# fretscanner2.net
KiCad netlist of a schematic drawn in EAGLE
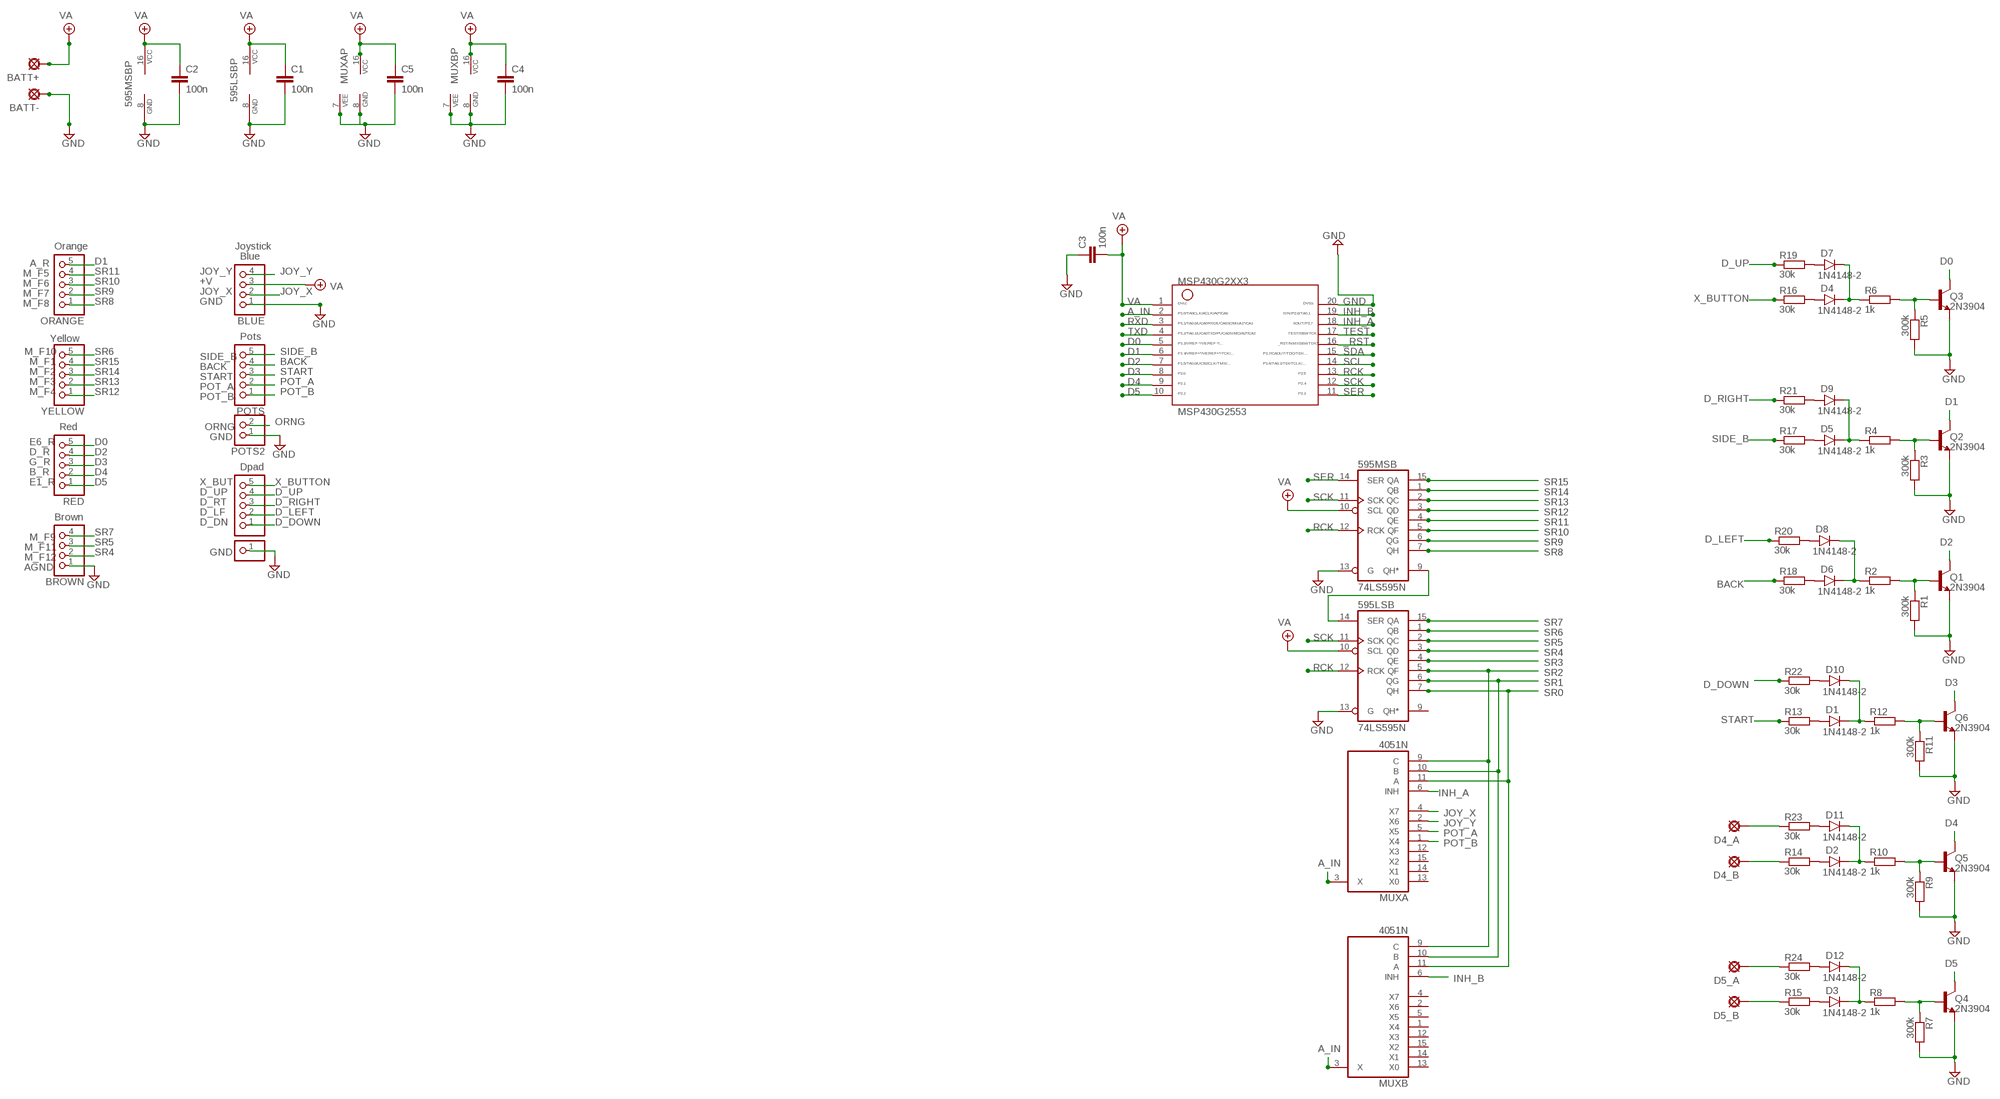
[diagram p0: schematic, sheet 1]

(export (version "E")
  (design (tool "Eeschema 10.0.6"))
  (components
    (comp (ref "595LSB")
      (value "74LS595N")
      (footprint "eagle-import:DIL16")
      (libsource (lib "eagle-import") (part "74595NLS"))
    )
    (comp (ref "595MSB")
      (value "74LS595N")
      (footprint "eagle-import:DIL16")
      (libsource (lib "eagle-import") (part "74595NLS"))
    )
    (comp (ref "BATT+")
      (value "PADL")
      (footprint "eagle-import:LONG")
      (libsource (lib "eagle-import") (part "PADL"))
    )
    (comp (ref "BATT-")
      (value "PADL")
      (footprint "eagle-import:LONG")
      (libsource (lib "eagle-import") (part "PADL"))
    )
    (comp (ref "BLUE")
      (value "PINHD-1X4")
      (footprint "eagle-import:1X04")
      (libsource (lib "eagle-import") (part "PINHD-1X4"))
    )
    (comp (ref "BROWN")
      (value "PINHD-1X4")
      (footprint "eagle-import:1X04")
      (libsource (lib "eagle-import") (part "PINHD-1X4"))
    )
    (comp (ref "C1")
      (value "100n")
      (footprint "eagle-import:050X030_050_3")
      (libsource (lib "eagle-import") (part "050X030_050"))
    )
    (comp (ref "C2")
      (value "100n")
      (footprint "eagle-import:050X030_050_3")
      (libsource (lib "eagle-import") (part "050X030_050"))
    )
    (comp (ref "C3")
      (value "100n")
      (footprint "eagle-import:050X030_050_3")
      (libsource (lib "eagle-import") (part "050X030_050"))
    )
    (comp (ref "C4")
      (value "100n")
      (footprint "eagle-import:050X030_050_3")
      (libsource (lib "eagle-import") (part "050X030_050"))
    )
    (comp (ref "C5")
      (value "100n")
      (footprint "eagle-import:050X030_050_3")
      (libsource (lib "eagle-import") (part "050X030_050"))
    )
    (comp (ref "D1")
      (value "1N4148-2")
      (footprint "eagle-import:DO35-2")
      (libsource (lib "eagle-import") (part "1N4148-2"))
    )
    (comp (ref "D2")
      (value "1N4148-2")
      (footprint "eagle-import:DO35-2")
      (libsource (lib "eagle-import") (part "1N4148-2"))
    )
    (comp (ref "D3")
      (value "1N4148-2")
      (footprint "eagle-import:DO35-2")
      (libsource (lib "eagle-import") (part "1N4148-2"))
    )
    (comp (ref "D4")
      (value "1N4148-2")
      (footprint "eagle-import:DO35-2")
      (libsource (lib "eagle-import") (part "1N4148-2"))
    )
    (comp (ref "D4_A")
      (value "PAD")
      (footprint "eagle-import:SQUARE")
      (libsource (lib "eagle-import") (part "PAD"))
    )
    (comp (ref "D4_B")
      (value "PAD")
      (footprint "eagle-import:SQUARE")
      (libsource (lib "eagle-import") (part "PAD"))
    )
    (comp (ref "D5")
      (value "1N4148-2")
      (footprint "eagle-import:DO35-2")
      (libsource (lib "eagle-import") (part "1N4148-2"))
    )
    (comp (ref "D5_A")
      (value "PAD")
      (footprint "eagle-import:SQUARE")
      (libsource (lib "eagle-import") (part "PAD"))
    )
    (comp (ref "D5_B")
      (value "PAD")
      (footprint "eagle-import:SQUARE")
      (libsource (lib "eagle-import") (part "PAD"))
    )
    (comp (ref "D6")
      (value "1N4148-2")
      (footprint "eagle-import:DO35-2")
      (libsource (lib "eagle-import") (part "1N4148-2"))
    )
    (comp (ref "D7")
      (value "1N4148-2")
      (footprint "eagle-import:DO35-2")
      (libsource (lib "eagle-import") (part "1N4148-2"))
    )
    (comp (ref "D8")
      (value "1N4148-2")
      (footprint "eagle-import:DO35-2")
      (libsource (lib "eagle-import") (part "1N4148-2"))
    )
    (comp (ref "D9")
      (value "1N4148-2")
      (footprint "eagle-import:DO35-2")
      (libsource (lib "eagle-import") (part "1N4148-2"))
    )
    (comp (ref "D10")
      (value "1N4148-2")
      (footprint "eagle-import:DO35-2")
      (libsource (lib "eagle-import") (part "1N4148-2"))
    )
    (comp (ref "D11")
      (value "1N4148-2")
      (footprint "eagle-import:DO35-2")
      (libsource (lib "eagle-import") (part "1N4148-2"))
    )
    (comp (ref "D12")
      (value "1N4148-2")
      (footprint "eagle-import:DO35-2")
      (libsource (lib "eagle-import") (part "1N4148-2"))
    )
    (comp (ref "DPAD")
      (value "PINHD-1X5")
      (footprint "eagle-import:1X05")
      (libsource (lib "eagle-import") (part "PINHD-1X5"))
    )
    (comp (ref "DPAD2")
      (value "PINHD-1X1")
      (footprint "eagle-import:1X01")
      (libsource (lib "eagle-import") (part "PINHD-1X1"))
    )
    (comp (ref "MSP430G2553")
      (value "G2XX3---N20")
      (footprint "eagle-import:N20")
      (libsource (lib "eagle-import") (part "G2XX3---N20"))
    )
    (comp (ref "MUXA")
      (value "4051N")
      (footprint "eagle-import:DIL16")
      (libsource (lib "eagle-import") (part "4051N"))
    )
    (comp (ref "MUXB")
      (value "4051N")
      (footprint "eagle-import:DIL16")
      (libsource (lib "eagle-import") (part "4051N"))
    )
    (comp (ref "ORANGE")
      (value "PINHD-1X5")
      (footprint "eagle-import:1X05")
      (libsource (lib "eagle-import") (part "PINHD-1X5"))
    )
    (comp (ref "POTS")
      (value "PINHD-1X5")
      (footprint "eagle-import:1X05")
      (libsource (lib "eagle-import") (part "PINHD-1X5"))
    )
    (comp (ref "POTS2")
      (value "PINHD-1X2")
      (footprint "eagle-import:1X02")
      (libsource (lib "eagle-import") (part "PINHD-1X2"))
    )
    (comp (ref "Q1")
      (value "2N3904")
      (footprint "eagle-import:TO92-")
      (libsource (lib "eagle-import") (part "2N3904"))
    )
    (comp (ref "Q2")
      (value "2N3904")
      (footprint "eagle-import:TO92-")
      (libsource (lib "eagle-import") (part "2N3904"))
    )
    (comp (ref "Q3")
      (value "2N3904")
      (footprint "eagle-import:TO92-")
      (libsource (lib "eagle-import") (part "2N3904"))
    )
    (comp (ref "Q4")
      (value "2N3904")
      (footprint "eagle-import:TO92-")
      (libsource (lib "eagle-import") (part "2N3904"))
    )
    (comp (ref "Q5")
      (value "2N3904")
      (footprint "eagle-import:TO92-")
      (libsource (lib "eagle-import") (part "2N3904"))
    )
    (comp (ref "Q6")
      (value "2N3904")
      (footprint "eagle-import:TO92-")
      (libsource (lib "eagle-import") (part "2N3904"))
    )
    (comp (ref "R1")
      (value "300k")
      (footprint "eagle-import:R0207_1V")
      (libsource (lib "eagle-import") (part "6MM-EU1"))
    )
    (comp (ref "R2")
      (value "1k")
      (footprint "eagle-import:R0207_3")
      (libsource (lib "eagle-import") (part "6MM-EU"))
    )
    (comp (ref "R3")
      (value "300k")
      (footprint "eagle-import:R0207_1V")
      (libsource (lib "eagle-import") (part "6MM-EU1"))
    )
    (comp (ref "R4")
      (value "1k")
      (footprint "eagle-import:R0207_3")
      (libsource (lib "eagle-import") (part "6MM-EU"))
    )
    (comp (ref "R5")
      (value "300k")
      (footprint "eagle-import:R0207_1V")
      (libsource (lib "eagle-import") (part "6MM-EU1"))
    )
    (comp (ref "R6")
      (value "1k")
      (footprint "eagle-import:R0207_3")
      (libsource (lib "eagle-import") (part "6MM-EU"))
    )
    (comp (ref "R7")
      (value "300k")
      (footprint "eagle-import:R0207_1V")
      (libsource (lib "eagle-import") (part "6MM-EU1"))
    )
    (comp (ref "R8")
      (value "1k")
      (footprint "eagle-import:R0207_3")
      (libsource (lib "eagle-import") (part "6MM-EU"))
    )
    (comp (ref "R9")
      (value "300k")
      (footprint "eagle-import:R0207_1V")
      (libsource (lib "eagle-import") (part "6MM-EU1"))
    )
    (comp (ref "R10")
      (value "1k")
      (footprint "eagle-import:R0207_3")
      (libsource (lib "eagle-import") (part "6MM-EU"))
    )
    (comp (ref "R11")
      (value "300k")
      (footprint "eagle-import:R0207_1V")
      (libsource (lib "eagle-import") (part "6MM-EU1"))
    )
    (comp (ref "R12")
      (value "1k")
      (footprint "eagle-import:R0207_3")
      (libsource (lib "eagle-import") (part "6MM-EU"))
    )
    (comp (ref "R13")
      (value "30k")
      (footprint "eagle-import:R0207_3")
      (libsource (lib "eagle-import") (part "6MM-EU"))
    )
    (comp (ref "R14")
      (value "30k")
      (footprint "eagle-import:R0207_3")
      (libsource (lib "eagle-import") (part "6MM-EU"))
    )
    (comp (ref "R15")
      (value "30k")
      (footprint "eagle-import:R0207_3")
      (libsource (lib "eagle-import") (part "6MM-EU"))
    )
    (comp (ref "R16")
      (value "30k")
      (footprint "eagle-import:R0207_3")
      (libsource (lib "eagle-import") (part "6MM-EU"))
    )
    (comp (ref "R17")
      (value "30k")
      (footprint "eagle-import:R0207_3")
      (libsource (lib "eagle-import") (part "6MM-EU"))
    )
    (comp (ref "R18")
      (value "30k")
      (footprint "eagle-import:R0207_3")
      (libsource (lib "eagle-import") (part "6MM-EU"))
    )
    (comp (ref "R19")
      (value "30k")
      (footprint "eagle-import:R0207_3")
      (libsource (lib "eagle-import") (part "6MM-EU"))
    )
    (comp (ref "R20")
      (value "30k")
      (footprint "eagle-import:R0207_3")
      (libsource (lib "eagle-import") (part "6MM-EU"))
    )
    (comp (ref "R21")
      (value "30k")
      (footprint "eagle-import:R0207_3")
      (libsource (lib "eagle-import") (part "6MM-EU"))
    )
    (comp (ref "R22")
      (value "30k")
      (footprint "eagle-import:R0207_3")
      (libsource (lib "eagle-import") (part "6MM-EU"))
    )
    (comp (ref "R23")
      (value "30k")
      (footprint "eagle-import:R0207_3")
      (libsource (lib "eagle-import") (part "6MM-EU"))
    )
    (comp (ref "R24")
      (value "30k")
      (footprint "eagle-import:R0207_3")
      (libsource (lib "eagle-import") (part "6MM-EU"))
    )
    (comp (ref "RED")
      (value "PINHD-1X5")
      (footprint "eagle-import:1X05")
      (libsource (lib "eagle-import") (part "PINHD-1X5"))
    )
    (comp (ref "YELLOW")
      (value "PINHD-1X5")
      (footprint "eagle-import:1X05")
      (libsource (lib "eagle-import") (part "PINHD-1X5"))
    )
  )
  (nets
    (net (code "1") (name "/A_IN") (class "Default")
      (node (ref "MSP430G2553") (pin "2") (pinfunction "2_2") (pintype "bidirectional"))
      (node (ref "MUXA") (pin "3") (pinfunction "X_3") (pintype "bidirectional"))
      (node (ref "MUXB") (pin "3") (pinfunction "X_3") (pintype "bidirectional"))
    )
    (net (code "2") (name "/BACK") (class "Default")
      (node (ref "POTS") (pin "4") (pinfunction "4_4") (pintype "passive"))
      (node (ref "R18") (pin "1") (pinfunction "1_1") (pintype "passive"))
    )
    (net (code "3") (name "/D0") (class "Default")
      (node (ref "MSP430G2553") (pin "5") (pinfunction "5_5") (pintype "bidirectional"))
      (node (ref "Q3") (pin "1") (pinfunction "C_1") (pintype "passive"))
      (node (ref "RED") (pin "5") (pinfunction "5_5") (pintype "passive"))
    )
    (net (code "4") (name "/D1") (class "Default")
      (node (ref "MSP430G2553") (pin "6") (pinfunction "6_6") (pintype "bidirectional"))
      (node (ref "ORANGE") (pin "5") (pinfunction "5_5") (pintype "passive"))
      (node (ref "Q2") (pin "1") (pinfunction "C_1") (pintype "passive"))
    )
    (net (code "5") (name "/D2") (class "Default")
      (node (ref "MSP430G2553") (pin "7") (pinfunction "7_7") (pintype "bidirectional"))
      (node (ref "Q1") (pin "1") (pinfunction "C_1") (pintype "passive"))
      (node (ref "RED") (pin "4") (pinfunction "4_4") (pintype "passive"))
    )
    (net (code "6") (name "/D3") (class "Default")
      (node (ref "MSP430G2553") (pin "8") (pinfunction "8_8") (pintype "bidirectional"))
      (node (ref "Q6") (pin "1") (pinfunction "C_1") (pintype "passive"))
      (node (ref "RED") (pin "3") (pinfunction "3_3") (pintype "passive"))
    )
    (net (code "7") (name "/D4") (class "Default")
      (node (ref "MSP430G2553") (pin "9") (pinfunction "9_9") (pintype "bidirectional"))
      (node (ref "Q5") (pin "1") (pinfunction "C_1") (pintype "passive"))
      (node (ref "RED") (pin "2") (pinfunction "2_2") (pintype "passive"))
    )
    (net (code "8") (name "/D5") (class "Default")
      (node (ref "MSP430G2553") (pin "10") (pinfunction "10_10") (pintype "bidirectional"))
      (node (ref "Q4") (pin "1") (pinfunction "C_1") (pintype "passive"))
      (node (ref "RED") (pin "1") (pinfunction "1_1") (pintype "passive"))
    )
    (net (code "9") (name "/D_DOWN") (class "Default")
      (node (ref "DPAD") (pin "1") (pinfunction "1_1") (pintype "passive"))
      (node (ref "R22") (pin "1") (pinfunction "1_1") (pintype "passive"))
    )
    (net (code "10") (name "/D_LEFT") (class "Default")
      (node (ref "DPAD") (pin "2") (pinfunction "2_2") (pintype "passive"))
      (node (ref "R20") (pin "1") (pinfunction "1_1") (pintype "passive"))
    )
    (net (code "11") (name "/D_RIGHT") (class "Default")
      (node (ref "DPAD") (pin "3") (pinfunction "3_3") (pintype "passive"))
      (node (ref "R21") (pin "1") (pinfunction "1_1") (pintype "passive"))
    )
    (net (code "12") (name "/D_UP") (class "Default")
      (node (ref "DPAD") (pin "4") (pinfunction "4_4") (pintype "passive"))
      (node (ref "R19") (pin "1") (pinfunction "1_1") (pintype "passive"))
    )
    (net (code "13") (name "/INH_A") (class "Default")
      (node (ref "MSP430G2553") (pin "18") (pinfunction "18_18") (pintype "bidirectional"))
      (node (ref "MUXA") (pin "6") (pinfunction "INH_6") (pintype "input"))
    )
    (net (code "14") (name "/INH_B") (class "Default")
      (node (ref "MSP430G2553") (pin "19") (pinfunction "19_19") (pintype "bidirectional"))
      (node (ref "MUXB") (pin "6") (pinfunction "INH_6") (pintype "input"))
    )
    (net (code "15") (name "/JOY_X") (class "Default")
      (node (ref "BLUE") (pin "2") (pinfunction "2_2") (pintype "passive"))
      (node (ref "MUXA") (pin "4") (pinfunction "X7_4") (pintype "bidirectional"))
    )
    (net (code "16") (name "/JOY_Y") (class "Default")
      (node (ref "BLUE") (pin "4") (pinfunction "4_4") (pintype "passive"))
      (node (ref "MUXA") (pin "2") (pinfunction "X6_2") (pintype "bidirectional"))
    )
    (net (code "17") (name "/ORNG") (class "Default")
      (node (ref "POTS2") (pin "2") (pinfunction "2_2") (pintype "passive"))
    )
    (net (code "18") (name "/POT_A") (class "Default")
      (node (ref "MUXA") (pin "5") (pinfunction "X5_5") (pintype "bidirectional"))
      (node (ref "POTS") (pin "2") (pinfunction "2_2") (pintype "passive"))
    )
    (net (code "19") (name "/POT_B") (class "Default")
      (node (ref "MUXA") (pin "1") (pinfunction "X4_1") (pintype "bidirectional"))
      (node (ref "POTS") (pin "1") (pinfunction "1_1") (pintype "passive"))
    )
    (net (code "20") (name "/RCK") (class "Default")
      (node (ref "595LSB") (pin "12") (pinfunction "RCK_12") (pintype "input"))
      (node (ref "595MSB") (pin "12") (pinfunction "RCK_12") (pintype "input"))
      (node (ref "MSP430G2553") (pin "13") (pinfunction "13_13") (pintype "bidirectional"))
    )
    (net (code "21") (name "/RXD") (class "Default")
      (node (ref "MSP430G2553") (pin "3") (pinfunction "3_3") (pintype "bidirectional"))
    )
    (net (code "22") (name "/SCK") (class "Default")
      (node (ref "595LSB") (pin "11") (pinfunction "SCK_11") (pintype "input"))
      (node (ref "595MSB") (pin "11") (pinfunction "SCK_11") (pintype "input"))
      (node (ref "MSP430G2553") (pin "12") (pinfunction "12_12") (pintype "bidirectional"))
    )
    (net (code "23") (name "/SCL") (class "Default")
      (node (ref "MSP430G2553") (pin "14") (pinfunction "14_14") (pintype "bidirectional"))
    )
    (net (code "24") (name "/SDA") (class "Default")
      (node (ref "MSP430G2553") (pin "15") (pinfunction "15_15") (pintype "bidirectional"))
    )
    (net (code "25") (name "/SER") (class "Default")
      (node (ref "595MSB") (pin "14") (pinfunction "SER_14") (pintype "input"))
      (node (ref "MSP430G2553") (pin "11") (pinfunction "11_11") (pintype "bidirectional"))
    )
    (net (code "26") (name "/SIDE_B") (class "Default")
      (node (ref "POTS") (pin "5") (pinfunction "5_5") (pintype "passive"))
      (node (ref "R17") (pin "1") (pinfunction "1_1") (pintype "passive"))
    )
    (net (code "27") (name "/SR0") (class "Default")
      (node (ref "595LSB") (pin "7") (pinfunction "QH_7") (pintype "tri_state"))
      (node (ref "MUXA") (pin "11") (pinfunction "A_11") (pintype "input"))
      (node (ref "MUXB") (pin "11") (pinfunction "A_11") (pintype "input"))
    )
    (net (code "28") (name "/SR1") (class "Default")
      (node (ref "595LSB") (pin "6") (pinfunction "QG_6") (pintype "tri_state"))
      (node (ref "MUXA") (pin "10") (pinfunction "B_10") (pintype "input"))
      (node (ref "MUXB") (pin "10") (pinfunction "B_10") (pintype "input"))
    )
    (net (code "29") (name "/SR2") (class "Default")
      (node (ref "595LSB") (pin "5") (pinfunction "QF_5") (pintype "tri_state"))
      (node (ref "MUXA") (pin "9") (pinfunction "C_9") (pintype "input"))
      (node (ref "MUXB") (pin "9") (pinfunction "C_9") (pintype "input"))
    )
    (net (code "30") (name "/SR3") (class "Default")
      (node (ref "595LSB") (pin "4") (pinfunction "QE_4") (pintype "tri_state"))
    )
    (net (code "31") (name "/SR4") (class "Default")
      (node (ref "595LSB") (pin "3") (pinfunction "QD_3") (pintype "tri_state"))
      (node (ref "BROWN") (pin "2") (pinfunction "2_2") (pintype "passive"))
    )
    (net (code "32") (name "/SR5") (class "Default")
      (node (ref "595LSB") (pin "2") (pinfunction "QC_2") (pintype "tri_state"))
      (node (ref "BROWN") (pin "3") (pinfunction "3_3") (pintype "passive"))
    )
    (net (code "33") (name "/SR6") (class "Default")
      (node (ref "595LSB") (pin "1") (pinfunction "QB_1") (pintype "tri_state"))
      (node (ref "YELLOW") (pin "5") (pinfunction "5_5") (pintype "passive"))
    )
    (net (code "34") (name "/SR7") (class "Default")
      (node (ref "595LSB") (pin "15") (pinfunction "QA_15") (pintype "tri_state"))
      (node (ref "BROWN") (pin "4") (pinfunction "4_4") (pintype "passive"))
    )
    (net (code "35") (name "/SR8") (class "Default")
      (node (ref "595MSB") (pin "7") (pinfunction "QH_7") (pintype "tri_state"))
      (node (ref "ORANGE") (pin "1") (pinfunction "1_1") (pintype "passive"))
    )
    (net (code "36") (name "/SR9") (class "Default")
      (node (ref "595MSB") (pin "6") (pinfunction "QG_6") (pintype "tri_state"))
      (node (ref "ORANGE") (pin "2") (pinfunction "2_2") (pintype "passive"))
    )
    (net (code "37") (name "/SR10") (class "Default")
      (node (ref "595MSB") (pin "5") (pinfunction "QF_5") (pintype "tri_state"))
      (node (ref "ORANGE") (pin "3") (pinfunction "3_3") (pintype "passive"))
    )
    (net (code "38") (name "/SR11") (class "Default")
      (node (ref "595MSB") (pin "4") (pinfunction "QE_4") (pintype "tri_state"))
      (node (ref "ORANGE") (pin "4") (pinfunction "4_4") (pintype "passive"))
    )
    (net (code "39") (name "/SR12") (class "Default")
      (node (ref "595MSB") (pin "3") (pinfunction "QD_3") (pintype "tri_state"))
      (node (ref "YELLOW") (pin "1") (pinfunction "1_1") (pintype "passive"))
    )
    (net (code "40") (name "/SR13") (class "Default")
      (node (ref "595MSB") (pin "2") (pinfunction "QC_2") (pintype "tri_state"))
      (node (ref "YELLOW") (pin "2") (pinfunction "2_2") (pintype "passive"))
    )
    (net (code "41") (name "/SR14") (class "Default")
      (node (ref "595MSB") (pin "1") (pinfunction "QB_1") (pintype "tri_state"))
      (node (ref "YELLOW") (pin "3") (pinfunction "3_3") (pintype "passive"))
    )
    (net (code "42") (name "/SR15") (class "Default")
      (node (ref "595MSB") (pin "15") (pinfunction "QA_15") (pintype "tri_state"))
      (node (ref "YELLOW") (pin "4") (pinfunction "4_4") (pintype "passive"))
    )
    (net (code "43") (name "/START") (class "Default")
      (node (ref "POTS") (pin "3") (pinfunction "3_3") (pintype "passive"))
      (node (ref "R13") (pin "1") (pinfunction "1_1") (pintype "passive"))
    )
    (net (code "44") (name "/TEST") (class "Default")
      (node (ref "MSP430G2553") (pin "17") (pinfunction "17_17") (pintype "bidirectional"))
    )
    (net (code "45") (name "/TXD") (class "Default")
      (node (ref "MSP430G2553") (pin "4") (pinfunction "4_4") (pintype "bidirectional"))
    )
    (net (code "46") (name "/X_BUTTON") (class "Default")
      (node (ref "DPAD") (pin "5") (pinfunction "5_5") (pintype "passive"))
      (node (ref "R16") (pin "1") (pinfunction "1_1") (pintype "passive"))
    )
    (net (code "47") (name "/_RST") (class "Default")
      (node (ref "MSP430G2553") (pin "16") (pinfunction "16_16") (pintype "bidirectional"))
    )
    (net (code "48") (name "GND") (class "Default")
      (node (ref "595LSB") (pin "13") (pinfunction "G_13") (pintype "input"))
      (node (ref "595LSB") (pin "8") (pinfunction "GND_8") (pintype "power_in"))
      (node (ref "595MSB") (pin "13") (pinfunction "G_13") (pintype "input"))
      (node (ref "595MSB") (pin "8") (pinfunction "GND_8") (pintype "power_in"))
      (node (ref "BATT-") (pin "1") (pinfunction "PAD_1") (pintype "passive"))
      (node (ref "BLUE") (pin "1") (pinfunction "1_1") (pintype "passive"))
      (node (ref "BROWN") (pin "1") (pinfunction "1_1") (pintype "passive"))
      (node (ref "C1") (pin "2") (pinfunction "2_2") (pintype "passive"))
      (node (ref "C2") (pin "2") (pinfunction "2_2") (pintype "passive"))
      (node (ref "C3") (pin "1") (pinfunction "1_1") (pintype "passive"))
      (node (ref "C4") (pin "2") (pinfunction "2_2") (pintype "passive"))
      (node (ref "C5") (pin "2") (pinfunction "2_2") (pintype "passive"))
      (node (ref "DPAD2") (pin "1") (pinfunction "1_1") (pintype "passive"))
      (node (ref "MSP430G2553") (pin "20") (pinfunction "20_20") (pintype "bidirectional"))
      (node (ref "MUXA") (pin "7") (pinfunction "VEE_7") (pintype "power_in"))
      (node (ref "MUXA") (pin "8") (pinfunction "GND_8") (pintype "power_in"))
      (node (ref "MUXB") (pin "7") (pinfunction "VEE_7") (pintype "power_in"))
      (node (ref "MUXB") (pin "8") (pinfunction "GND_8") (pintype "power_in"))
      (node (ref "POTS2") (pin "1") (pinfunction "1_1") (pintype "passive"))
      (node (ref "Q1") (pin "3") (pinfunction "E_3") (pintype "passive"))
      (node (ref "Q2") (pin "3") (pinfunction "E_3") (pintype "passive"))
      (node (ref "Q3") (pin "3") (pinfunction "E_3") (pintype "passive"))
      (node (ref "Q4") (pin "3") (pinfunction "E_3") (pintype "passive"))
      (node (ref "Q5") (pin "3") (pinfunction "E_3") (pintype "passive"))
      (node (ref "Q6") (pin "3") (pinfunction "E_3") (pintype "passive"))
      (node (ref "R1") (pin "2") (pinfunction "2_2") (pintype "passive"))
      (node (ref "R11") (pin "2") (pinfunction "2_2") (pintype "passive"))
      (node (ref "R3") (pin "2") (pinfunction "2_2") (pintype "passive"))
      (node (ref "R5") (pin "2") (pinfunction "2_2") (pintype "passive"))
      (node (ref "R7") (pin "2") (pinfunction "2_2") (pintype "passive"))
      (node (ref "R9") (pin "2") (pinfunction "2_2") (pintype "passive"))
    )
    (net (code "49") (name "Net-(595LSBA-SER)") (class "Default")
      (node (ref "595LSB") (pin "14") (pinfunction "SER_14") (pintype "input"))
      (node (ref "595MSB") (pin "9") (pinfunction "QH*_9") (pintype "tri_state"))
    )
    (net (code "50") (name "Net-(D1-PadA)") (class "Default")
      (node (ref "D1") (pin "A") (pinfunction "A_A") (pintype "passive"))
      (node (ref "R13") (pin "2") (pinfunction "2_2") (pintype "passive"))
    )
    (net (code "51") (name "Net-(D1-PadC)") (class "Default")
      (node (ref "D1") (pin "C") (pinfunction "C_C") (pintype "passive"))
      (node (ref "D10") (pin "C") (pinfunction "C_C") (pintype "passive"))
      (node (ref "R12") (pin "1") (pinfunction "1_1") (pintype "passive"))
    )
    (net (code "52") (name "Net-(D2-PadA)") (class "Default")
      (node (ref "D2") (pin "A") (pinfunction "A_A") (pintype "passive"))
      (node (ref "R14") (pin "2") (pinfunction "2_2") (pintype "passive"))
    )
    (net (code "53") (name "Net-(D3-PadA)") (class "Default")
      (node (ref "D3") (pin "A") (pinfunction "A_A") (pintype "passive"))
      (node (ref "R15") (pin "2") (pinfunction "2_2") (pintype "passive"))
    )
    (net (code "54") (name "Net-(D4-PadA)") (class "Default")
      (node (ref "D4") (pin "A") (pinfunction "A_A") (pintype "passive"))
      (node (ref "R16") (pin "2") (pinfunction "2_2") (pintype "passive"))
    )
    (net (code "55") (name "Net-(D4-PadC)") (class "Default")
      (node (ref "D4") (pin "C") (pinfunction "C_C") (pintype "passive"))
      (node (ref "D7") (pin "C") (pinfunction "C_C") (pintype "passive"))
      (node (ref "R6") (pin "1") (pinfunction "1_1") (pintype "passive"))
    )
    (net (code "56") (name "Net-(D4_A-PAD)") (class "Default")
      (node (ref "D4_A") (pin "1") (pinfunction "PAD_1") (pintype "passive"))
      (node (ref "R23") (pin "1") (pinfunction "1_1") (pintype "passive"))
    )
    (net (code "57") (name "Net-(D4_B-PAD)") (class "Default")
      (node (ref "D4_B") (pin "1") (pinfunction "PAD_1") (pintype "passive"))
      (node (ref "R14") (pin "1") (pinfunction "1_1") (pintype "passive"))
    )
    (net (code "58") (name "Net-(D5-PadA)") (class "Default")
      (node (ref "D5") (pin "A") (pinfunction "A_A") (pintype "passive"))
      (node (ref "R17") (pin "2") (pinfunction "2_2") (pintype "passive"))
    )
    (net (code "59") (name "Net-(D5-PadC)") (class "Default")
      (node (ref "D5") (pin "C") (pinfunction "C_C") (pintype "passive"))
      (node (ref "D9") (pin "C") (pinfunction "C_C") (pintype "passive"))
      (node (ref "R4") (pin "1") (pinfunction "1_1") (pintype "passive"))
    )
    (net (code "60") (name "Net-(D5_A-PAD)") (class "Default")
      (node (ref "D5_A") (pin "1") (pinfunction "PAD_1") (pintype "passive"))
      (node (ref "R24") (pin "1") (pinfunction "1_1") (pintype "passive"))
    )
    (net (code "61") (name "Net-(D5_B-PAD)") (class "Default")
      (node (ref "D5_B") (pin "1") (pinfunction "PAD_1") (pintype "passive"))
      (node (ref "R15") (pin "1") (pinfunction "1_1") (pintype "passive"))
    )
    (net (code "62") (name "Net-(D6-PadA)") (class "Default")
      (node (ref "D6") (pin "A") (pinfunction "A_A") (pintype "passive"))
      (node (ref "R18") (pin "2") (pinfunction "2_2") (pintype "passive"))
    )
    (net (code "63") (name "Net-(D6-PadC)") (class "Default")
      (node (ref "D6") (pin "C") (pinfunction "C_C") (pintype "passive"))
      (node (ref "D8") (pin "C") (pinfunction "C_C") (pintype "passive"))
      (node (ref "R2") (pin "1") (pinfunction "1_1") (pintype "passive"))
    )
    (net (code "64") (name "Net-(D7-PadA)") (class "Default")
      (node (ref "D7") (pin "A") (pinfunction "A_A") (pintype "passive"))
      (node (ref "R19") (pin "2") (pinfunction "2_2") (pintype "passive"))
    )
    (net (code "65") (name "Net-(D8-PadA)") (class "Default")
      (node (ref "D8") (pin "A") (pinfunction "A_A") (pintype "passive"))
      (node (ref "R20") (pin "2") (pinfunction "2_2") (pintype "passive"))
    )
    (net (code "66") (name "Net-(D9-PadA)") (class "Default")
      (node (ref "D9") (pin "A") (pinfunction "A_A") (pintype "passive"))
      (node (ref "R21") (pin "2") (pinfunction "2_2") (pintype "passive"))
    )
    (net (code "67") (name "Net-(D10-PadA)") (class "Default")
      (node (ref "D10") (pin "A") (pinfunction "A_A") (pintype "passive"))
      (node (ref "R22") (pin "2") (pinfunction "2_2") (pintype "passive"))
    )
    (net (code "68") (name "Net-(D11-PadA)") (class "Default")
      (node (ref "D11") (pin "A") (pinfunction "A_A") (pintype "passive"))
      (node (ref "R23") (pin "2") (pinfunction "2_2") (pintype "passive"))
    )
    (net (code "69") (name "Net-(D11-PadC)") (class "Default")
      (node (ref "D11") (pin "C") (pinfunction "C_C") (pintype "passive"))
      (node (ref "D2") (pin "C") (pinfunction "C_C") (pintype "passive"))
      (node (ref "R10") (pin "1") (pinfunction "1_1") (pintype "passive"))
    )
    (net (code "70") (name "Net-(D12-PadA)") (class "Default")
      (node (ref "D12") (pin "A") (pinfunction "A_A") (pintype "passive"))
      (node (ref "R24") (pin "2") (pinfunction "2_2") (pintype "passive"))
    )
    (net (code "71") (name "Net-(D12-PadC)") (class "Default")
      (node (ref "D12") (pin "C") (pinfunction "C_C") (pintype "passive"))
      (node (ref "D3") (pin "C") (pinfunction "C_C") (pintype "passive"))
      (node (ref "R8") (pin "1") (pinfunction "1_1") (pintype "passive"))
    )
    (net (code "72") (name "Net-(Q1-B)") (class "Default")
      (node (ref "Q1") (pin "2") (pinfunction "B_2") (pintype "passive"))
      (node (ref "R1") (pin "1") (pinfunction "1_1") (pintype "passive"))
      (node (ref "R2") (pin "2") (pinfunction "2_2") (pintype "passive"))
    )
    (net (code "73") (name "Net-(Q2-B)") (class "Default")
      (node (ref "Q2") (pin "2") (pinfunction "B_2") (pintype "passive"))
      (node (ref "R3") (pin "1") (pinfunction "1_1") (pintype "passive"))
      (node (ref "R4") (pin "2") (pinfunction "2_2") (pintype "passive"))
    )
    (net (code "74") (name "Net-(Q3-B)") (class "Default")
      (node (ref "Q3") (pin "2") (pinfunction "B_2") (pintype "passive"))
      (node (ref "R5") (pin "1") (pinfunction "1_1") (pintype "passive"))
      (node (ref "R6") (pin "2") (pinfunction "2_2") (pintype "passive"))
    )
    (net (code "75") (name "Net-(Q4-B)") (class "Default")
      (node (ref "Q4") (pin "2") (pinfunction "B_2") (pintype "passive"))
      (node (ref "R7") (pin "1") (pinfunction "1_1") (pintype "passive"))
      (node (ref "R8") (pin "2") (pinfunction "2_2") (pintype "passive"))
    )
    (net (code "76") (name "Net-(Q5-B)") (class "Default")
      (node (ref "Q5") (pin "2") (pinfunction "B_2") (pintype "passive"))
      (node (ref "R10") (pin "2") (pinfunction "2_2") (pintype "passive"))
      (node (ref "R9") (pin "1") (pinfunction "1_1") (pintype "passive"))
    )
    (net (code "77") (name "Net-(Q6-B)") (class "Default")
      (node (ref "Q6") (pin "2") (pinfunction "B_2") (pintype "passive"))
      (node (ref "R11") (pin "1") (pinfunction "1_1") (pintype "passive"))
      (node (ref "R12") (pin "2") (pinfunction "2_2") (pintype "passive"))
    )
    (net (code "78") (name "VA") (class "Default")
      (node (ref "595LSB") (pin "10") (pinfunction "SCL_10") (pintype "input"))
      (node (ref "595LSB") (pin "16") (pinfunction "VCC_16") (pintype "power_in"))
      (node (ref "595MSB") (pin "10") (pinfunction "SCL_10") (pintype "input"))
      (node (ref "595MSB") (pin "16") (pinfunction "VCC_16") (pintype "power_in"))
      (node (ref "BATT+") (pin "1") (pinfunction "PAD_1") (pintype "passive"))
      (node (ref "BLUE") (pin "3") (pinfunction "3_3") (pintype "passive"))
      (node (ref "C1") (pin "1") (pinfunction "1_1") (pintype "passive"))
      (node (ref "C2") (pin "1") (pinfunction "1_1") (pintype "passive"))
      (node (ref "C3") (pin "2") (pinfunction "2_2") (pintype "passive"))
      (node (ref "C4") (pin "1") (pinfunction "1_1") (pintype "passive"))
      (node (ref "C5") (pin "1") (pinfunction "1_1") (pintype "passive"))
      (node (ref "MSP430G2553") (pin "1") (pinfunction "1_1") (pintype "bidirectional"))
      (node (ref "MUXA") (pin "16") (pinfunction "VCC_16") (pintype "power_in"))
      (node (ref "MUXB") (pin "16") (pinfunction "VCC_16") (pintype "power_in"))
    )
    (net (code "79") (name "unconnected-(595LSBA-QH*-Pad9)") (class "Default")
      (node (ref "595LSB") (pin "9") (pinfunction "QH*_9") (pintype "tri_state"))
    )
    (net (code "80") (name "unconnected-(MUXAA-X0-Pad13)") (class "Default")
      (node (ref "MUXA") (pin "13") (pinfunction "X0_13") (pintype "bidirectional"))
    )
    (net (code "81") (name "unconnected-(MUXAA-X1-Pad14)") (class "Default")
      (node (ref "MUXA") (pin "14") (pinfunction "X1_14") (pintype "bidirectional"))
    )
    (net (code "82") (name "unconnected-(MUXAA-X2-Pad15)") (class "Default")
      (node (ref "MUXA") (pin "15") (pinfunction "X2_15") (pintype "bidirectional"))
    )
    (net (code "83") (name "unconnected-(MUXAA-X3-Pad12)") (class "Default")
      (node (ref "MUXA") (pin "12") (pinfunction "X3_12") (pintype "bidirectional"))
    )
    (net (code "84") (name "unconnected-(MUXBA-X0-Pad13)") (class "Default")
      (node (ref "MUXB") (pin "13") (pinfunction "X0_13") (pintype "bidirectional"))
    )
    (net (code "85") (name "unconnected-(MUXBA-X1-Pad14)") (class "Default")
      (node (ref "MUXB") (pin "14") (pinfunction "X1_14") (pintype "bidirectional"))
    )
    (net (code "86") (name "unconnected-(MUXBA-X2-Pad15)") (class "Default")
      (node (ref "MUXB") (pin "15") (pinfunction "X2_15") (pintype "bidirectional"))
    )
    (net (code "87") (name "unconnected-(MUXBA-X3-Pad12)") (class "Default")
      (node (ref "MUXB") (pin "12") (pinfunction "X3_12") (pintype "bidirectional"))
    )
    (net (code "88") (name "unconnected-(MUXBA-X4-Pad1)") (class "Default")
      (node (ref "MUXB") (pin "1") (pinfunction "X4_1") (pintype "bidirectional"))
    )
    (net (code "89") (name "unconnected-(MUXBA-X5-Pad5)") (class "Default")
      (node (ref "MUXB") (pin "5") (pinfunction "X5_5") (pintype "bidirectional"))
    )
    (net (code "90") (name "unconnected-(MUXBA-X6-Pad2)") (class "Default")
      (node (ref "MUXB") (pin "2") (pinfunction "X6_2") (pintype "bidirectional"))
    )
    (net (code "91") (name "unconnected-(MUXBA-X7-Pad4)") (class "Default")
      (node (ref "MUXB") (pin "4") (pinfunction "X7_4") (pintype "bidirectional"))
    )
  )
)
